# Option_PMIC_RK818.net
KiCad netlist of a schematic drawn in Altium Designer
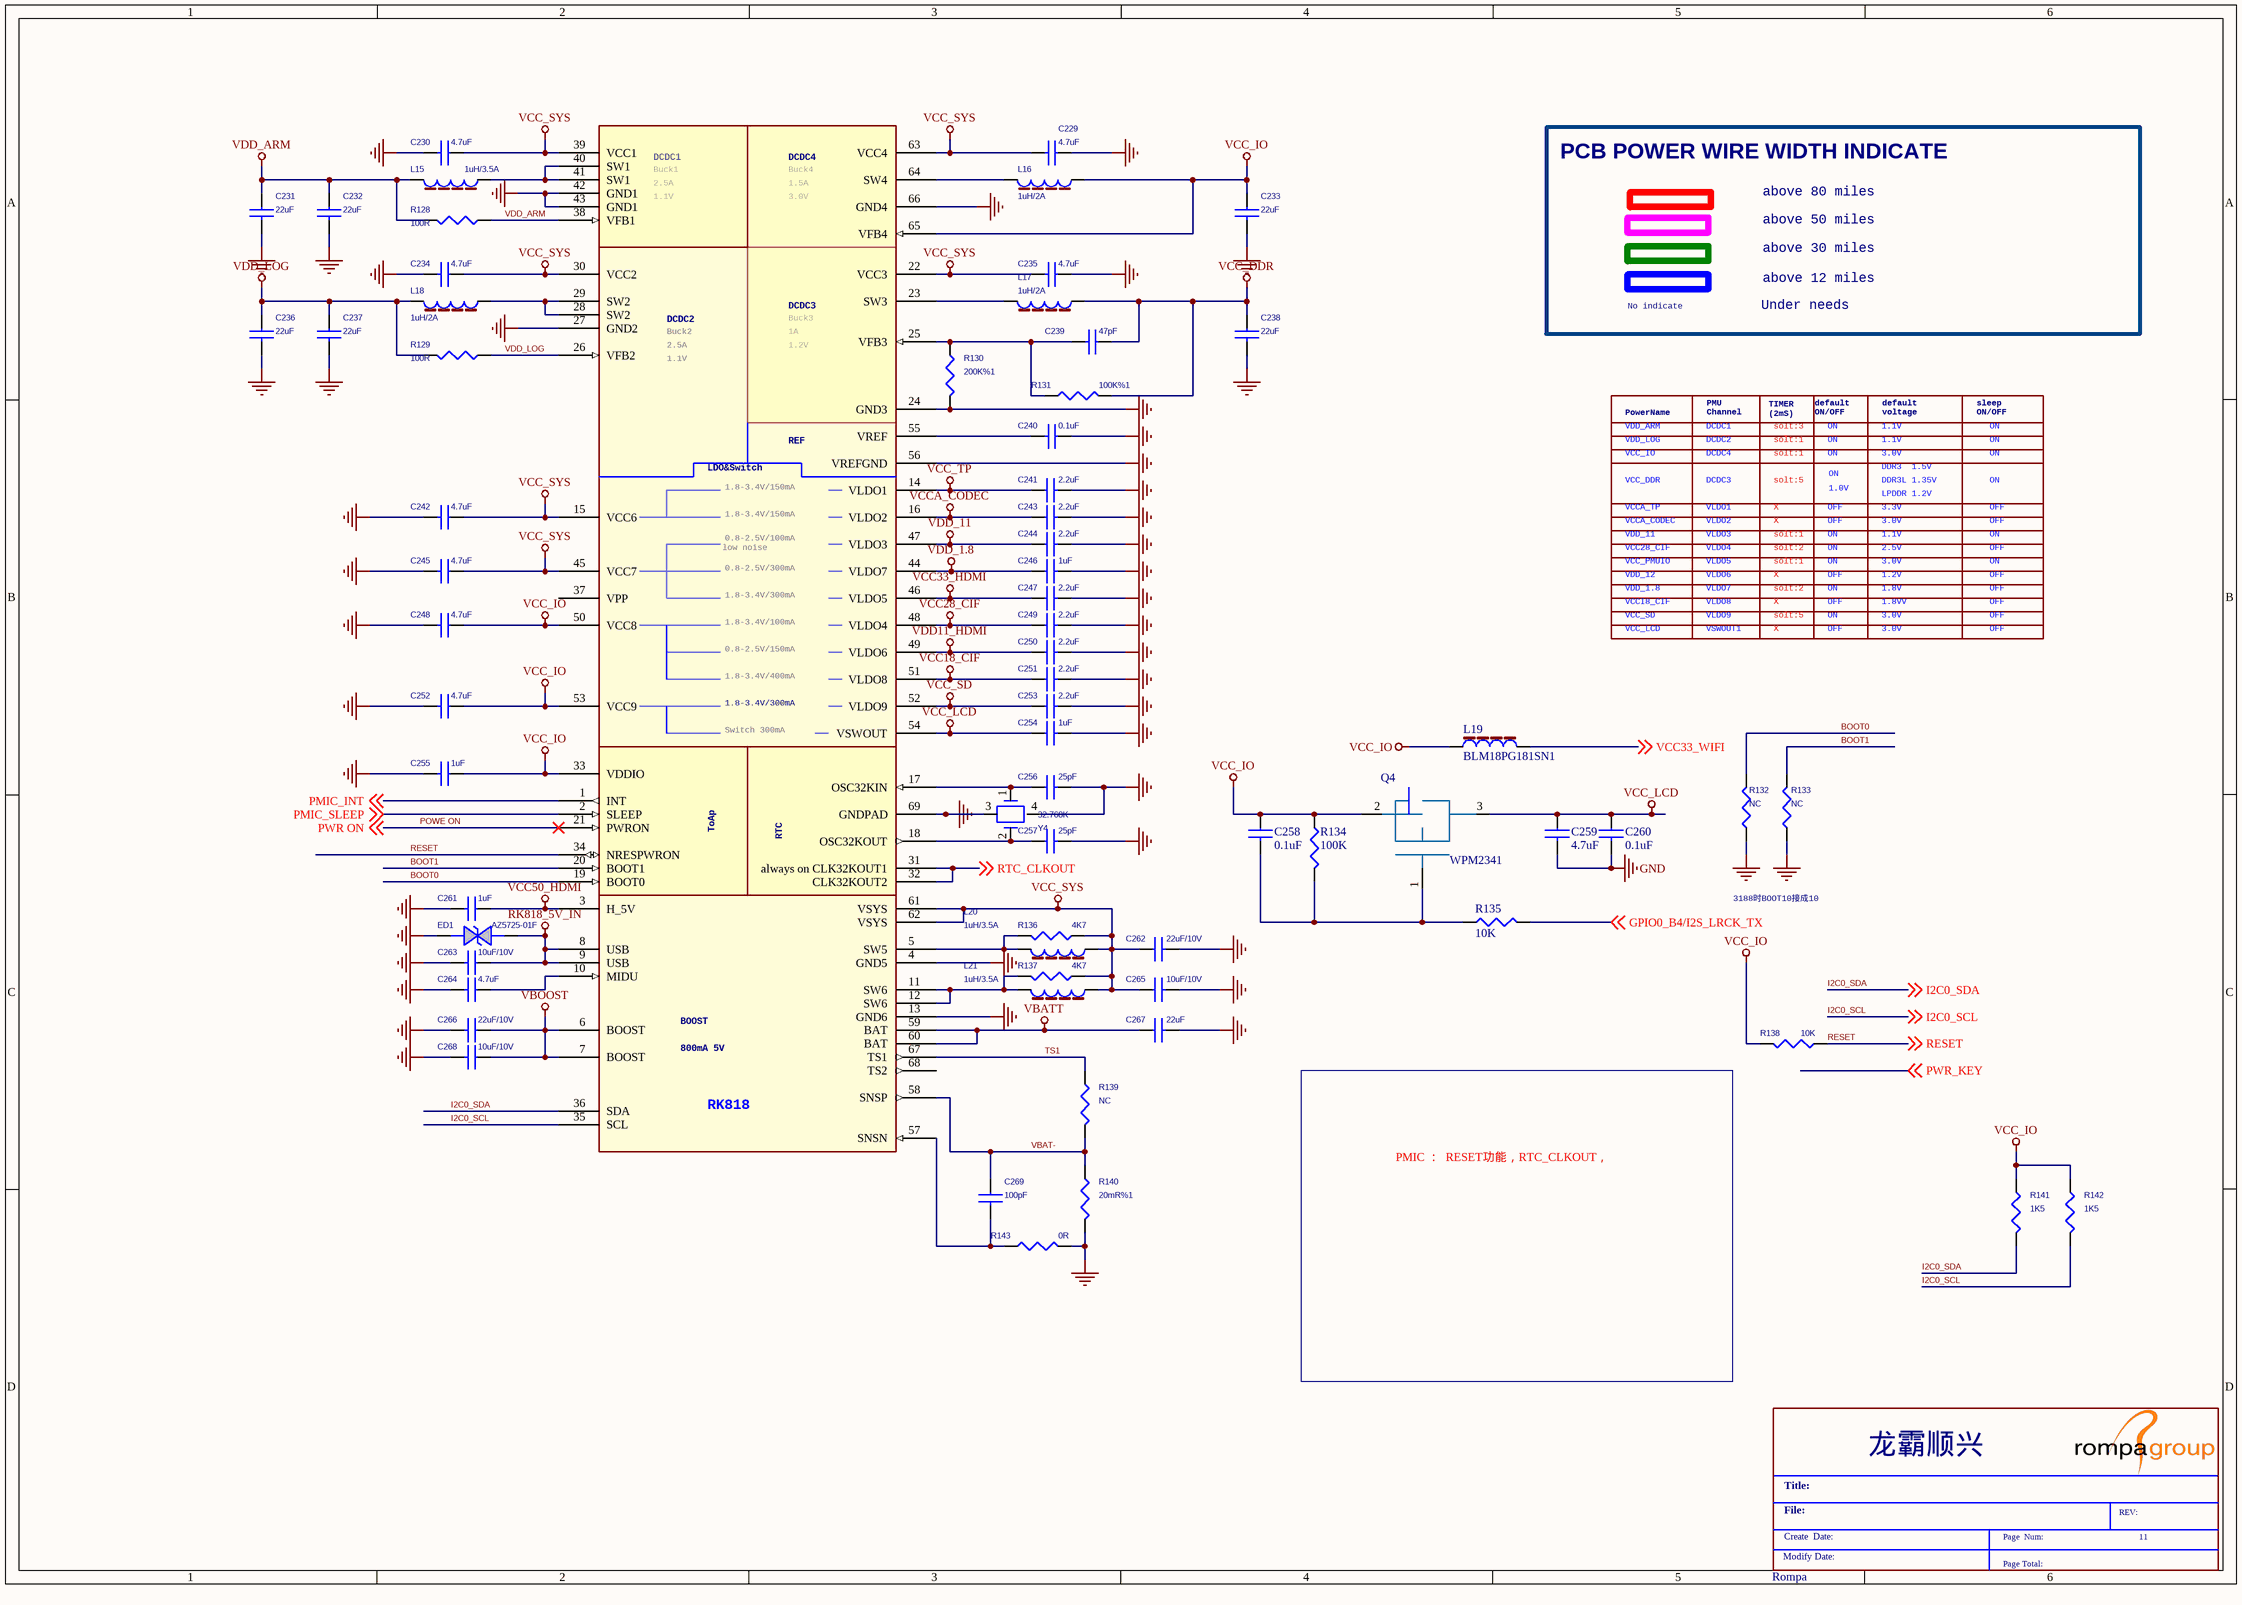
[diagram p0: Option_PMIC_RK818.SchDoc]

(export (version "E")
  (design (tool "Eeschema 10.0.6"))
  (components
    (comp (ref "C229") (value "4.7uF") (footprint "C0603") (libsource (lib "*") (part "CAP NP_4")))
    (comp (ref "C230") (value "4.7uF") (footprint "C0603") (libsource (lib "*") (part "CAP NP_4")))
    (comp (ref "C231") (value "22uF") (footprint "C0805") (libsource (lib "*") (part "CAP NP_4")))
    (comp (ref "C232") (value "22uF") (footprint "C0805") (libsource (lib "*") (part "CAP NP_4")))
    (comp (ref "C233") (value "22uF") (footprint "C0805") (libsource (lib "*") (part "CAP NP_4")))
    (comp (ref "C234") (value "4.7uF") (footprint "C0603") (libsource (lib "*") (part "CAP NP_4")))
    (comp (ref "C235") (value "4.7uF") (footprint "C0603") (libsource (lib "*") (part "CAP NP_4")))
    (comp (ref "C236") (value "22uF") (footprint "C0805") (libsource (lib "*") (part "CAP NP_4")))
    (comp (ref "C237") (value "22uF") (footprint "C0805") (libsource (lib "*") (part "CAP NP_4")))
    (comp (ref "C238") (value "22uF") (footprint "C0805") (libsource (lib "*") (part "CAP NP_4")))
    (comp (ref "C239") (value "47pF") (footprint "C0402") (libsource (lib "*") (part "CAP NP_4")))
    (comp (ref "C240") (value "0.1uF") (footprint "C0402") (libsource (lib "*") (part "CAP NP_4")))
    (comp (ref "C241") (value "2.2uF") (footprint "C0402") (libsource (lib "*") (part "CAP NP_4")))
    (comp (ref "C242") (value "4.7uF") (footprint "C0603") (libsource (lib "*") (part "CAP NP_4")))
    (comp (ref "C243") (value "2.2uF") (footprint "C0402") (libsource (lib "*") (part "CAP NP_4")))
    (comp (ref "C244") (value "2.2uF") (footprint "C0402") (libsource (lib "*") (part "CAP NP_4")))
    (comp (ref "C245") (value "4.7uF") (footprint "C0603") (libsource (lib "*") (part "CAP NP_4")))
    (comp (ref "C246") (value "1uF") (footprint "C0402") (libsource (lib "*") (part "CAP NP_4")))
    (comp (ref "C247") (value "2.2uF") (footprint "C0402") (libsource (lib "*") (part "CAP NP_4")))
    (comp (ref "C248") (value "4.7uF") (footprint "C0603") (libsource (lib "*") (part "CAP NP_4")))
    (comp (ref "C249") (value "2.2uF") (footprint "C0402") (libsource (lib "*") (part "CAP NP_4")))
    (comp (ref "C250") (value "2.2uF") (footprint "C0402") (libsource (lib "*") (part "CAP NP_4")))
    (comp (ref "C251") (value "2.2uF") (footprint "C0402") (libsource (lib "*") (part "CAP NP_4")))
    (comp (ref "C252") (value "4.7uF") (footprint "C0603") (libsource (lib "*") (part "CAP NP_4")))
    (comp (ref "C253") (value "2.2uF") (footprint "C0402") (libsource (lib "*") (part "CAP NP_4")))
    (comp (ref "C254") (value "1uF") (footprint "C0402") (libsource (lib "*") (part "CAP NP_4")))
    (comp (ref "C255") (value "1uF") (footprint "C0402") (libsource (lib "*") (part "CAP NP_4")))
    (comp (ref "C256") (value "25pF") (footprint "C0402") (libsource (lib "*") (part "CAP NP_4")))
    (comp (ref "C257") (value "25pF") (footprint "C0402") (libsource (lib "*") (part "CAP NP_4")))
    (comp (ref "C258")
      (value "0.1uF")
      (footprint "C0402")
      (libsource (lib "RK3128_BETA_V03_20151231_Library") (part "CAP NP"))
    )
    (comp (ref "C259")
      (value "4.7uF")
      (footprint "C0402")
      (libsource (lib "RK3128_BETA_V03_20151231_Library") (part "CAP NP"))
    )
    (comp (ref "C260")
      (value "0.1uF")
      (footprint "C0402")
      (libsource (lib "RK3128_BETA_V03_20151231_Library") (part "CAP NP"))
    )
    (comp (ref "C261") (value "1uF") (footprint "C0402") (libsource (lib "*") (part "CAP NP_4")))
    (comp (ref "C262") (value "22uF/10V") (footprint "C1206") (libsource (lib "*") (part "CAP NP_4")))
    (comp (ref "C263") (value "10uF/10V") (footprint "C0805") (libsource (lib "*") (part "CAP NP_4")))
    (comp (ref "C264") (value "4.7uF") (footprint "C0603") (libsource (lib "*") (part "CAP NP_4")))
    (comp (ref "C265") (value "10uF/10V") (footprint "C0805") (libsource (lib "*") (part "CAP NP_4")))
    (comp (ref "C266") (value "22uF/10V") (footprint "C1206") (libsource (lib "*") (part "CAP NP_4")))
    (comp (ref "C267") (value "22uF") (footprint "C0805") (libsource (lib "*") (part "CAP NP_4")))
    (comp (ref "C268") (value "10uF/10V") (footprint "C0805") (libsource (lib "*") (part "CAP NP_4")))
    (comp (ref "C269") (value "100pF") (footprint "C0402") (libsource (lib "*") (part "CAP NP_4")))
    (comp (ref "ED1")
      (value "AZ5725-01F")
      (footprint "E0402")
      (description "ESD")
      (libsource (lib "*") (part "DIODE BI-DIR TRIG"))
    )
    (comp (ref "L15") (value "1uH/3.5A") (footprint "IND-4X4") (libsource (lib "*") (part "INDUCTOR_2")))
    (comp (ref "L16") (value "1uH/2A") (footprint "IND-3X3") (libsource (lib "*") (part "INDUCTOR_2")))
    (comp (ref "L17") (value "1uH/2A") (footprint "IND-3X3") (libsource (lib "*") (part "INDUCTOR_2")))
    (comp (ref "L18") (value "1uH/2A") (footprint "IND-3X3") (libsource (lib "*") (part "INDUCTOR_2")))
    (comp (ref "L19")
      (value "BLM18PG181SN1")
      (footprint "L0603")
      (libsource (lib "RK3128_BETA_V03_20151231_Library") (part "INDUCTOR_2"))
    )
    (comp (ref "L20") (value "1uH/3.5A") (footprint "IND-4X4") (libsource (lib "*") (part "INDUCTOR_2")))
    (comp (ref "L21") (value "1uH/3.5A") (footprint "IND-4X4") (libsource (lib "*") (part "INDUCTOR_2")))
    (comp (ref "Q4") (value "WPM2341") (footprint "SOT23") (libsource (lib "iguide_custom") (part "WPM2341")))
    (comp (ref "R128")
      (value "100R")
      (footprint "R0402")
      (description "RES,thick film,47KOhm,+/-5%,1/16W,SMD0402")
      (libsource (lib "*") (part "RESISTOR_1"))
    )
    (comp (ref "R129")
      (value "100R")
      (footprint "R0402")
      (description "RES,thick film,47KOhm,+/-5%,1/16W,SMD0402")
      (libsource (lib "*") (part "RESISTOR_1"))
    )
    (comp (ref "R130")
      (value "200K%1")
      (footprint "R0402")
      (description "RES,thick film,47KOhm,+/-5%,1/16W,SMD0402")
      (libsource (lib "*") (part "RESISTOR_1"))
    )
    (comp (ref "R131")
      (value "100K%1")
      (footprint "R0402")
      (description "RES,thick film,47KOhm,+/-5%,1/16W,SMD0402")
      (libsource (lib "*") (part "RESISTOR_1"))
    )
    (comp (ref "R132")
      (value "NC")
      (footprint "R0402")
      (description "RES,thick film,47KOhm,+/-5%,1/16W,SMD0402")
      (libsource (lib "*") (part "RESISTOR_1"))
    )
    (comp (ref "R133")
      (value "NC")
      (footprint "R0402")
      (description "RES,thick film,47KOhm,+/-5%,1/16W,SMD0402")
      (libsource (lib "*") (part "RESISTOR_1"))
    )
    (comp (ref "R134")
      (value "100K")
      (footprint "R0402")
      (libsource (lib "RK3128_BETA_V03_20151231_Library") (part "RESISTOR"))
    )
    (comp (ref "R135")
      (value "10K")
      (footprint "R0402")
      (libsource (lib "RK3128_BETA_V03_20151231_Library") (part "RESISTOR"))
    )
    (comp (ref "R136")
      (value "4K7")
      (footprint "R0402")
      (description "RES,thick film,47KOhm,+/-5%,1/16W,SMD0402")
      (libsource (lib "*") (part "RESISTOR_1"))
    )
    (comp (ref "R137")
      (value "4K7")
      (footprint "R0402")
      (description "RES,thick film,47KOhm,+/-5%,1/16W,SMD0402")
      (libsource (lib "*") (part "RESISTOR_1"))
    )
    (comp (ref "R138")
      (value "10K")
      (footprint "R0402")
      (description "RES,thick film,47KOhm,+/-5%,1/16W,SMD0402")
      (libsource (lib "*") (part "RESISTOR_1"))
    )
    (comp (ref "R139")
      (value "NC")
      (footprint "R0402")
      (description "贴片电阻")
      (libsource (lib "*") (part "RESISTOR_1"))
    )
    (comp (ref "R140")
      (value "20mR%1")
      (footprint "R1210")
      (description "贴片电阻")
      (libsource (lib "*") (part "RESISTOR_1"))
    )
    (comp (ref "R141")
      (value "1K5")
      (footprint "R0402")
      (description "ROHS CHIP RES 4.7K 1/16W 5%")
      (libsource (lib "*") (part "RES 1B"))
    )
    (comp (ref "R142")
      (value "1K5")
      (footprint "R0402")
      (description "ROHS CHIP RES 4.7K 1/16W 5%")
      (libsource (lib "*") (part "RES 1B"))
    )
    (comp (ref "R143")
      (value "0R")
      (footprint "R0402")
      (description "贴片电阻")
      (libsource (lib "*") (part "RESISTOR_1"))
    )
    (comp (ref "U19") (value "RK818") (footprint "QFN68") (libsource (lib "*") (part "RK818_1")))
    (comp (ref "Y4")
      (value "32.768K")
      (footprint "CRY_MC146")
      (description "Crystal,32.768KHz,+/-30ppm,12pF,MC146,-10°C ~ +60   °C")
      (libsource (lib "*") (part "CRYSTAL_0"))
    )
  )
  (nets
    (net (code "1") (name "/BOOT0") (class "Default")
      (node (ref "R132") (pin "1") (pinfunction "1_1") (pintype "passive"))
      (node (ref "U19") (pin "19") (pinfunction "BOOT0_19") (pintype "input"))
    )
    (net (code "2") (name "/BOOT1") (class "Default")
      (node (ref "R133") (pin "1") (pinfunction "1_1") (pintype "passive"))
      (node (ref "U19") (pin "20") (pinfunction "BOOT1_20") (pintype "input"))
    )
    (net (code "3") (name "/TS1") (class "Default")
      (node (ref "R139") (pin "1") (pinfunction "1_1") (pintype "passive"))
      (node (ref "U19") (pin "67") (pinfunction "TS1_67") (pintype "output"))
    )
    (net (code "4") (name "/VBAT-") (class "Default")
      (node (ref "C269") (pin "1") (pinfunction "1_1") (pintype "passive"))
      (node (ref "R139") (pin "2") (pinfunction "2_2") (pintype "passive"))
      (node (ref "R140") (pin "1") (pinfunction "1_1") (pintype "passive"))
      (node (ref "U19") (pin "58") (pinfunction "SNSP_58") (pintype "output"))
    )
    (net (code "5") (name "GND") (class "Default")
      (node (ref "C229") (pin "1") (pinfunction "1_1") (pintype "passive"))
      (node (ref "C230") (pin "2") (pinfunction "2_2") (pintype "passive"))
      (node (ref "C231") (pin "2") (pinfunction "2_2") (pintype "passive"))
      (node (ref "C232") (pin "2") (pinfunction "2_2") (pintype "passive"))
      (node (ref "C233") (pin "2") (pinfunction "2_2") (pintype "passive"))
      (node (ref "C234") (pin "2") (pinfunction "2_2") (pintype "passive"))
      (node (ref "C235") (pin "1") (pinfunction "1_1") (pintype "passive"))
      (node (ref "C236") (pin "2") (pinfunction "2_2") (pintype "passive"))
      (node (ref "C237") (pin "2") (pinfunction "2_2") (pintype "passive"))
      (node (ref "C238") (pin "2") (pinfunction "2_2") (pintype "passive"))
      (node (ref "C240") (pin "1") (pinfunction "1_1") (pintype "passive"))
      (node (ref "C241") (pin "2") (pinfunction "2_2") (pintype "passive"))
      (node (ref "C242") (pin "2") (pinfunction "2_2") (pintype "passive"))
      (node (ref "C243") (pin "2") (pinfunction "2_2") (pintype "passive"))
      (node (ref "C244") (pin "2") (pinfunction "2_2") (pintype "passive"))
      (node (ref "C245") (pin "2") (pinfunction "2_2") (pintype "passive"))
      (node (ref "C246") (pin "2") (pinfunction "2_2") (pintype "passive"))
      (node (ref "C247") (pin "2") (pinfunction "2_2") (pintype "passive"))
      (node (ref "C248") (pin "2") (pinfunction "2_2") (pintype "passive"))
      (node (ref "C249") (pin "2") (pinfunction "2_2") (pintype "passive"))
      (node (ref "C250") (pin "2") (pinfunction "2_2") (pintype "passive"))
      (node (ref "C251") (pin "2") (pinfunction "2_2") (pintype "passive"))
      (node (ref "C252") (pin "2") (pinfunction "2_2") (pintype "passive"))
      (node (ref "C253") (pin "2") (pinfunction "2_2") (pintype "passive"))
      (node (ref "C254") (pin "2") (pinfunction "2_2") (pintype "passive"))
      (node (ref "C255") (pin "2") (pinfunction "2_2") (pintype "passive"))
      (node (ref "C256") (pin "2") (pinfunction "2_2") (pintype "passive"))
      (node (ref "C257") (pin "2") (pinfunction "2_2") (pintype "passive"))
      (node (ref "C259") (pin "2") (pinfunction "2_2") (pintype "passive"))
      (node (ref "C260") (pin "2") (pinfunction "2_2") (pintype "passive"))
      (node (ref "C261") (pin "2") (pinfunction "2_2") (pintype "passive"))
      (node (ref "C262") (pin "2") (pinfunction "2_2") (pintype "passive"))
      (node (ref "C263") (pin "2") (pinfunction "2_2") (pintype "passive"))
      (node (ref "C264") (pin "2") (pinfunction "2_2") (pintype "passive"))
      (node (ref "C265") (pin "2") (pinfunction "2_2") (pintype "passive"))
      (node (ref "C266") (pin "2") (pinfunction "2_2") (pintype "passive"))
      (node (ref "C267") (pin "2") (pinfunction "2_2") (pintype "passive"))
      (node (ref "C268") (pin "2") (pinfunction "2_2") (pintype "passive"))
      (node (ref "ED1") (pin "1") (pinfunction "1_1") (pintype "passive"))
      (node (ref "R130") (pin "1") (pinfunction "1_1") (pintype "passive"))
      (node (ref "R132") (pin "2") (pinfunction "2_2") (pintype "passive"))
      (node (ref "R133") (pin "2") (pinfunction "2_2") (pintype "passive"))
      (node (ref "R140") (pin "2") (pinfunction "2_2") (pintype "passive"))
      (node (ref "R143") (pin "2") (pinfunction "2_2") (pintype "passive"))
      (node (ref "U19") (pin "13") (pinfunction "GND6_13") (pintype "power_in"))
      (node (ref "U19") (pin "24") (pinfunction "GND3_24") (pintype "power_in"))
      (node (ref "U19") (pin "27") (pinfunction "GND2_27") (pintype "power_in"))
      (node (ref "U19") (pin "4") (pinfunction "GND5_4") (pintype "power_in"))
      (node (ref "U19") (pin "42") (pinfunction "GND1_42") (pintype "power_in"))
      (node (ref "U19") (pin "43") (pinfunction "GND1_43") (pintype "power_in"))
      (node (ref "U19") (pin "56") (pinfunction "VREFGND_56") (pintype "power_in"))
      (node (ref "U19") (pin "66") (pinfunction "GND4_66") (pintype "power_in"))
      (node (ref "U19") (pin "69") (pinfunction "GNDPAD_69") (pintype "power_in"))
      (node (ref "Y4") (pin "3") (pinfunction "3_3") (pintype "passive"))
      (node (ref "Y4") (pin "4") (pinfunction "4_4") (pintype "passive"))
    )
    (net (code "6") (name "GPIO0_B4{slash}I2S_LRCK_TX") (class "Default")
      (node (ref "R135") (pin "2") (pinfunction "2_2") (pintype "passive"))
    )
    (net (code "7") (name "I2C0_SCL") (class "Default")
      (node (ref "R142") (pin "2") (pinfunction "2_2") (pintype "passive"))
      (node (ref "U19") (pin "35") (pinfunction "SCL_35") (pintype "open_collector"))
    )
    (net (code "8") (name "I2C0_SDA") (class "Default")
      (node (ref "R141") (pin "2") (pinfunction "2_2") (pintype "passive"))
      (node (ref "U19") (pin "36") (pinfunction "SDA_36") (pintype "open_collector"))
    )
    (net (code "9") (name "Net-(C258-Pad2)") (class "Default")
      (node (ref "C258") (pin "2") (pinfunction "2_2") (pintype "passive"))
      (node (ref "Q4") (pin "1") (pinfunction "1_1") (pintype "passive"))
      (node (ref "R134") (pin "2") (pinfunction "2_2") (pintype "passive"))
      (node (ref "R135") (pin "1") (pinfunction "1_1") (pintype "passive"))
    )
    (net (code "10") (name "Net-(L15-Pad2)") (class "Default")
      (node (ref "L15") (pin "2") (pinfunction "2_2") (pintype "passive"))
      (node (ref "U19") (pin "40") (pinfunction "SW1_40") (pintype "power_in"))
      (node (ref "U19") (pin "41") (pinfunction "SW1_41") (pintype "power_in"))
    )
    (net (code "11") (name "Net-(L18-Pad2)") (class "Default")
      (node (ref "L18") (pin "2") (pinfunction "2_2") (pintype "passive"))
      (node (ref "U19") (pin "28") (pinfunction "SW2_28") (pintype "power_in"))
      (node (ref "U19") (pin "29") (pinfunction "SW2_29") (pintype "power_in"))
    )
    (net (code "12") (name "Net-(L21-Pad1)") (class "Default")
      (node (ref "L21") (pin "1") (pinfunction "1_1") (pintype "passive"))
      (node (ref "R137") (pin "2") (pinfunction "2_2") (pintype "passive"))
      (node (ref "U19") (pin "11") (pinfunction "SW6_11") (pintype "power_in"))
      (node (ref "U19") (pin "12") (pinfunction "SW6_12") (pintype "power_in"))
    )
    (net (code "13") (name "Net-(U19-MIDU)") (class "Default")
      (node (ref "C264") (pin "1") (pinfunction "1_1") (pintype "passive"))
      (node (ref "U19") (pin "10") (pinfunction "MIDU_10") (pintype "input"))
    )
    (net (code "14") (name "Net-(U19-OSC32KIN)") (class "Default")
      (node (ref "C256") (pin "1") (pinfunction "1_1") (pintype "passive"))
      (node (ref "U19") (pin "17") (pinfunction "OSC32KIN_17") (pintype "input"))
      (node (ref "Y4") (pin "1") (pinfunction "1_1") (pintype "passive"))
    )
    (net (code "15") (name "Net-(U19-OSC32KOUT)") (class "Default")
      (node (ref "C257") (pin "1") (pinfunction "1_1") (pintype "passive"))
      (node (ref "U19") (pin "18") (pinfunction "OSC32KOUT_18") (pintype "output"))
      (node (ref "Y4") (pin "2") (pinfunction "2_2") (pintype "passive"))
    )
    (net (code "16") (name "Net-(U19-SNSN)") (class "Default")
      (node (ref "C269") (pin "2") (pinfunction "2_2") (pintype "passive"))
      (node (ref "R143") (pin "1") (pinfunction "1_1") (pintype "passive"))
      (node (ref "U19") (pin "57") (pinfunction "SNSN_57") (pintype "input"))
    )
    (net (code "17") (name "Net-(U19-SW3)") (class "Default")
      (node (ref "L17") (pin "1") (pinfunction "1_1") (pintype "passive"))
      (node (ref "U19") (pin "23") (pinfunction "SW3_23") (pintype "power_in"))
    )
    (net (code "18") (name "Net-(U19-SW4)") (class "Default")
      (node (ref "L16") (pin "1") (pinfunction "1_1") (pintype "passive"))
      (node (ref "U19") (pin "64") (pinfunction "SW4_64") (pintype "power_in"))
    )
    (net (code "19") (name "Net-(U19-SW5)") (class "Default")
      (node (ref "L20") (pin "1") (pinfunction "1_1") (pintype "passive"))
      (node (ref "R136") (pin "2") (pinfunction "2_2") (pintype "passive"))
      (node (ref "U19") (pin "5") (pinfunction "SW5_5") (pintype "power_in"))
    )
    (net (code "20") (name "Net-(U19-VFB3)") (class "Default")
      (node (ref "C239") (pin "2") (pinfunction "2_2") (pintype "passive"))
      (node (ref "R130") (pin "2") (pinfunction "2_2") (pintype "passive"))
      (node (ref "R131") (pin "2") (pinfunction "2_2") (pintype "passive"))
      (node (ref "U19") (pin "25") (pinfunction "VFB3_25") (pintype "input"))
    )
    (net (code "21") (name "Net-(U19-VREF)") (class "Default")
      (node (ref "C240") (pin "2") (pinfunction "2_2") (pintype "passive"))
      (node (ref "U19") (pin "55") (pinfunction "VREF_55") (pintype "power_in"))
    )
    (net (code "22") (name "PMIC_INT") (class "Default")
      (node (ref "U19") (pin "1") (pinfunction "INT_1") (pintype "output"))
    )
    (net (code "23") (name "PMIC_SLEEP") (class "Default")
      (node (ref "U19") (pin "2") (pinfunction "SLEEP_2") (pintype "input"))
    )
    (net (code "24") (name "PWR ON") (class "Default")
      (node (ref "U19") (pin "21") (pinfunction "PWRON_21") (pintype "input"))
    )
    (net (code "26") (name "RESET") (class "Default")
      (node (ref "R138") (pin "2") (pinfunction "2_2") (pintype "passive"))
      (node (ref "U19") (pin "34") (pinfunction "NRESPWRON_34") (pintype "bidirectional"))
    )
    (net (code "27") (name "RK818_5V_IN") (class "Default")
      (node (ref "C263") (pin "1") (pinfunction "1_1") (pintype "passive"))
      (node (ref "ED1") (pin "2") (pinfunction "2_2") (pintype "passive"))
      (node (ref "U19") (pin "8") (pinfunction "USB_8") (pintype "power_in"))
      (node (ref "U19") (pin "9") (pinfunction "USB_9") (pintype "power_in"))
    )
    (net (code "28") (name "RTC_CLKOUT") (class "Default")
      (node (ref "U19") (pin "31") (pinfunction "always_on_CLK32KOUT1_31") (pintype "open_collector"))
      (node (ref "U19") (pin "32") (pinfunction "CLK32KOUT2_32") (pintype "open_collector"))
    )
    (net (code "29") (name "VBATT") (class "Default")
      (node (ref "C267") (pin "1") (pinfunction "1_1") (pintype "passive"))
      (node (ref "U19") (pin "59") (pinfunction "BAT_59") (pintype "power_in"))
      (node (ref "U19") (pin "60") (pinfunction "BAT_60") (pintype "power_in"))
    )
    (net (code "30") (name "VBOOST") (class "Default")
      (node (ref "C266") (pin "1") (pinfunction "1_1") (pintype "passive"))
      (node (ref "C268") (pin "1") (pinfunction "1_1") (pintype "passive"))
      (node (ref "U19") (pin "6") (pinfunction "BOOST_6") (pintype "power_in"))
      (node (ref "U19") (pin "7") (pinfunction "BOOST_7") (pintype "power_in"))
    )
    (net (code "31") (name "VCC18_CIF") (class "Default")
      (node (ref "C251") (pin "1") (pinfunction "1_1") (pintype "passive"))
      (node (ref "U19") (pin "51") (pinfunction "VLDO8_51") (pintype "power_in"))
    )
    (net (code "32") (name "VCC28_CIF") (class "Default")
      (node (ref "C249") (pin "1") (pinfunction "1_1") (pintype "passive"))
      (node (ref "U19") (pin "48") (pinfunction "VLDO4_48") (pintype "power_in"))
    )
    (net (code "33") (name "VCC33_HDMI") (class "Default")
      (node (ref "C247") (pin "1") (pinfunction "1_1") (pintype "passive"))
      (node (ref "U19") (pin "46") (pinfunction "VLDO5_46") (pintype "power_in"))
    )
    (net (code "34") (name "VCC33_WIFI") (class "Default")
      (node (ref "L19") (pin "2") (pinfunction "2_2") (pintype "passive"))
    )
    (net (code "35") (name "VCC50_HDMI") (class "Default")
      (node (ref "C261") (pin "1") (pinfunction "1_1") (pintype "passive"))
      (node (ref "U19") (pin "3") (pinfunction "H_5V_3") (pintype "power_in"))
    )
    (net (code "36") (name "VCCA_CODEC") (class "Default")
      (node (ref "C243") (pin "1") (pinfunction "1_1") (pintype "passive"))
      (node (ref "U19") (pin "16") (pinfunction "VLDO2_16") (pintype "power_in"))
    )
    (net (code "37") (name "VCC_DDR") (class "Default")
      (node (ref "C238") (pin "1") (pinfunction "1_1") (pintype "passive"))
      (node (ref "C239") (pin "1") (pinfunction "1_1") (pintype "passive"))
      (node (ref "L17") (pin "2") (pinfunction "2_2") (pintype "passive"))
      (node (ref "R131") (pin "1") (pinfunction "1_1") (pintype "passive"))
    )
    (net (code "38") (name "VCC_IO") (class "Default")
      (node (ref "C233") (pin "1") (pinfunction "1_1") (pintype "passive"))
      (node (ref "C248") (pin "1") (pinfunction "1_1") (pintype "passive"))
      (node (ref "C252") (pin "1") (pinfunction "1_1") (pintype "passive"))
      (node (ref "C255") (pin "1") (pinfunction "1_1") (pintype "passive"))
      (node (ref "C258") (pin "1") (pinfunction "1_1") (pintype "passive"))
      (node (ref "L16") (pin "2") (pinfunction "2_2") (pintype "passive"))
      (node (ref "L19") (pin "1") (pinfunction "1_1") (pintype "passive"))
      (node (ref "R134") (pin "1") (pinfunction "1_1") (pintype "passive"))
      (node (ref "R138") (pin "1") (pinfunction "1_1") (pintype "passive"))
      (node (ref "R141") (pin "1") (pinfunction "1_1") (pintype "passive"))
      (node (ref "R142") (pin "1") (pinfunction "1_1") (pintype "passive"))
      (node (ref "U19") (pin "33") (pinfunction "VDDIO_33") (pintype "power_in"))
      (node (ref "U19") (pin "50") (pinfunction "VCC8_50") (pintype "power_in"))
      (node (ref "U19") (pin "53") (pinfunction "VCC9_53") (pintype "power_in"))
      (node (ref "U19") (pin "65") (pinfunction "VFB4_65") (pintype "input"))
    )
    (net (code "39") (name "VCC_LCD") (class "Default")
      (node (ref "C254") (pin "1") (pinfunction "1_1") (pintype "passive"))
      (node (ref "C259") (pin "1") (pinfunction "1_1") (pintype "passive"))
      (node (ref "C260") (pin "1") (pinfunction "1_1") (pintype "passive"))
      (node (ref "U19") (pin "54") (pinfunction "VSWOUT_54") (pintype "power_in"))
    )
    (net (code "40") (name "VCC_SD") (class "Default")
      (node (ref "C253") (pin "1") (pinfunction "1_1") (pintype "passive"))
      (node (ref "U19") (pin "52") (pinfunction "VLDO9_52") (pintype "power_in"))
    )
    (net (code "41") (name "VCC_SYS") (class "Default")
      (node (ref "C229") (pin "2") (pinfunction "2_2") (pintype "passive"))
      (node (ref "C230") (pin "1") (pinfunction "1_1") (pintype "passive"))
      (node (ref "C234") (pin "1") (pinfunction "1_1") (pintype "passive"))
      (node (ref "C235") (pin "2") (pinfunction "2_2") (pintype "passive"))
      (node (ref "C242") (pin "1") (pinfunction "1_1") (pintype "passive"))
      (node (ref "C245") (pin "1") (pinfunction "1_1") (pintype "passive"))
      (node (ref "C262") (pin "1") (pinfunction "1_1") (pintype "passive"))
      (node (ref "C265") (pin "1") (pinfunction "1_1") (pintype "passive"))
      (node (ref "L20") (pin "2") (pinfunction "2_2") (pintype "passive"))
      (node (ref "L21") (pin "2") (pinfunction "2_2") (pintype "passive"))
      (node (ref "R136") (pin "1") (pinfunction "1_1") (pintype "passive"))
      (node (ref "R137") (pin "1") (pinfunction "1_1") (pintype "passive"))
      (node (ref "U19") (pin "15") (pinfunction "VCC6_15") (pintype "power_in"))
      (node (ref "U19") (pin "22") (pinfunction "VCC3_22") (pintype "power_in"))
      (node (ref "U19") (pin "30") (pinfunction "VCC2_30") (pintype "power_in"))
      (node (ref "U19") (pin "39") (pinfunction "VCC1_39") (pintype "power_in"))
      (node (ref "U19") (pin "45") (pinfunction "VCC7_45") (pintype "power_in"))
      (node (ref "U19") (pin "61") (pinfunction "VSYS_61") (pintype "power_in"))
      (node (ref "U19") (pin "62") (pinfunction "VSYS_62") (pintype "power_in"))
      (node (ref "U19") (pin "63") (pinfunction "VCC4_63") (pintype "power_in"))
    )
    (net (code "42") (name "VCC_TP") (class "Default")
      (node (ref "C241") (pin "1") (pinfunction "1_1") (pintype "passive"))
      (node (ref "U19") (pin "14") (pinfunction "VLDO1_14") (pintype "power_in"))
    )
    (net (code "43") (name "VDD11_HDMI") (class "Default")
      (node (ref "C250") (pin "1") (pinfunction "1_1") (pintype "passive"))
      (node (ref "U19") (pin "49") (pinfunction "VLDO6_49") (pintype "power_in"))
    )
    (net (code "44") (name "VDD_1.8") (class "Default")
      (node (ref "C246") (pin "1") (pinfunction "1_1") (pintype "passive"))
      (node (ref "U19") (pin "44") (pinfunction "VLDO7_44") (pintype "power_in"))
    )
    (net (code "45") (name "VDD_11") (class "Default")
      (node (ref "C244") (pin "1") (pinfunction "1_1") (pintype "passive"))
      (node (ref "U19") (pin "47") (pinfunction "VLDO3_47") (pintype "power_in"))
    )
    (net (code "46") (name "VDD_ARM") (class "Default")
      (node (ref "C231") (pin "1") (pinfunction "1_1") (pintype "passive"))
      (node (ref "C232") (pin "1") (pinfunction "1_1") (pintype "passive"))
      (node (ref "L15") (pin "1") (pinfunction "1_1") (pintype "passive"))
      (node (ref "R128") (pin "1") (pinfunction "1_1") (pintype "passive"))
      (node (ref "R128") (pin "2") (pinfunction "2_2") (pintype "passive"))
      (node (ref "U19") (pin "38") (pinfunction "VFB1_38") (pintype "input"))
    )
    (net (code "47") (name "VDD_LOG") (class "Default")
      (node (ref "C236") (pin "1") (pinfunction "1_1") (pintype "passive"))
      (node (ref "C237") (pin "1") (pinfunction "1_1") (pintype "passive"))
      (node (ref "L18") (pin "1") (pinfunction "1_1") (pintype "passive"))
      (node (ref "R129") (pin "1") (pinfunction "1_1") (pintype "passive"))
      (node (ref "R129") (pin "2") (pinfunction "2_2") (pintype "passive"))
      (node (ref "U19") (pin "26") (pinfunction "VFB2_26") (pintype "input"))
    )
    (net (code "48") (name "unconnected-(Q4-Pad2)") (class "Default")
      (node (ref "Q4") (pin "2") (pinfunction "2_2") (pintype "passive"))
    )
    (net (code "49") (name "unconnected-(Q4-Pad3)") (class "Default")
      (node (ref "Q4") (pin "3") (pinfunction "3_3") (pintype "passive"))
    )
    (net (code "50") (name "unconnected-(U19-TS2-Pad68)") (class "Default")
      (node (ref "U19") (pin "68") (pinfunction "TS2_68") (pintype "output"))
    )
    (net (code "51") (name "unconnected-(U19-VPP-Pad37)") (class "Default")
      (node (ref "U19") (pin "37") (pinfunction "VPP_37") (pintype "passive"))
    )
  )
)
